# kaaEmonitor_2v01.net
KiCad netlist of a schematic drawn in EAGLE
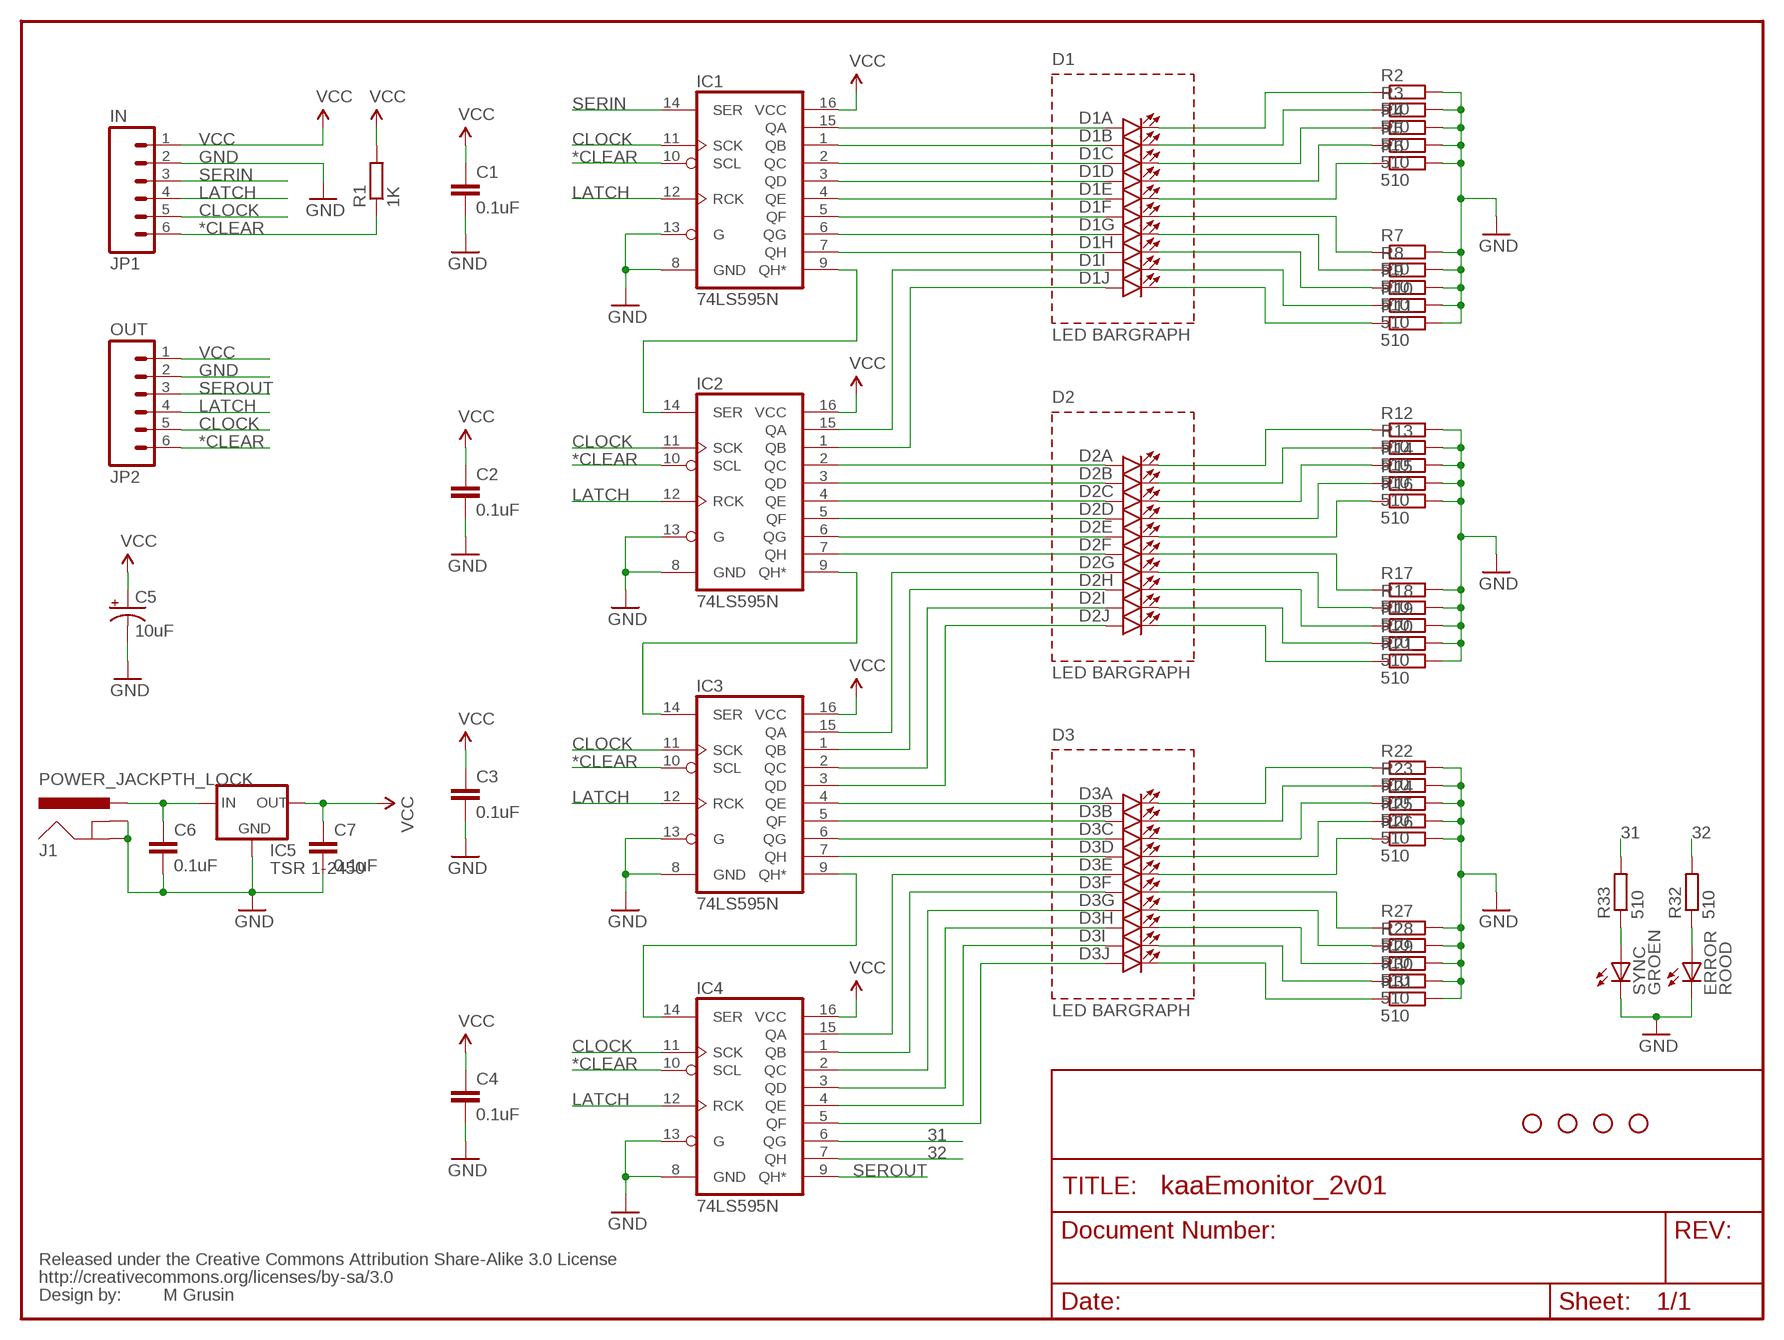
[diagram p0: schematic, sheet 1]

(export (version "E")
  (design (tool "Eeschema 10.0.6"))
  (components
    (comp (ref "C1")
      (value "0.1uF")
      (footprint "eagle-import:CAP-PTH-SMALL2")
      (libsource (lib "eagle-import") (part "CAPPTH2"))
    )
    (comp (ref "C2")
      (value "0.1uF")
      (footprint "eagle-import:CAP-PTH-SMALL2")
      (libsource (lib "eagle-import") (part "CAPPTH2"))
    )
    (comp (ref "C3")
      (value "0.1uF")
      (footprint "eagle-import:CAP-PTH-SMALL2")
      (libsource (lib "eagle-import") (part "CAPPTH2"))
    )
    (comp (ref "C4")
      (value "0.1uF")
      (footprint "eagle-import:CAP-PTH-SMALL2")
      (libsource (lib "eagle-import") (part "CAPPTH2"))
    )
    (comp (ref "C5")
      (value "10uF")
      (footprint "eagle-import:CPOL-RADIAL-10UF-25V")
      (libsource (lib "eagle-import") (part "CAP_POLPTH2"))
    )
    (comp (ref "C6")
      (value "0.1uF")
      (footprint "eagle-import:CAP-PTH-SMALL2")
      (libsource (lib "eagle-import") (part "CAPPTH2"))
    )
    (comp (ref "C7")
      (value "0.1uF")
      (footprint "eagle-import:CAP-PTH-SMALL2")
      (libsource (lib "eagle-import") (part "CAPPTH2"))
    )
    (comp (ref "D1")
      (value "LED_BARGRAPH_10")
      (footprint "eagle-import:LED_BARGAPH_10")
      (libsource (lib "eagle-import") (part "LED_BARGRAPH_10"))
    )
    (comp (ref "D2")
      (value "LED_BARGRAPH_10")
      (footprint "eagle-import:LED_BARGAPH_10")
      (libsource (lib "eagle-import") (part "LED_BARGRAPH_10"))
    )
    (comp (ref "D3")
      (value "LED_BARGRAPH_10")
      (footprint "eagle-import:LED_BARGAPH_10")
      (libsource (lib "eagle-import") (part "LED_BARGRAPH_10"))
    )
    (comp (ref "ERROR")
      (value "ROOD")
      (footprint "eagle-import:LED3MM")
      (libsource (lib "eagle-import") (part "LED3MM"))
    )
    (comp (ref "IC1")
      (value "74LS595N")
      (footprint "eagle-import:DIL16")
      (libsource (lib "eagle-import") (part "74595NLS"))
    )
    (comp (ref "IC2")
      (value "74LS595N")
      (footprint "eagle-import:DIL16")
      (libsource (lib "eagle-import") (part "74595NLS"))
    )
    (comp (ref "IC3")
      (value "74LS595N")
      (footprint "eagle-import:DIL16")
      (libsource (lib "eagle-import") (part "74595NLS"))
    )
    (comp (ref "IC4")
      (value "74LS595N")
      (footprint "eagle-import:DIL16")
      (libsource (lib "eagle-import") (part "74595NLS"))
    )
    (comp (ref "IC5")
      (value "TSR 1-2450")
      (footprint "eagle-import:TO220-IGO")
      (libsource (lib "eagle-import") (part "V_REG_78XXSINK"))
    )
    (comp (ref "J1")
      (value "POWER_JACKPTH_LOCK")
      (footprint "eagle-import:POWER_JACK_PTH_LOCK")
      (libsource (lib "eagle-import") (part "POWER_JACKPTH_LOCK"))
    )
    (comp (ref "JP1")
      (value "IN")
      (footprint "eagle-import:1X06")
      (libsource (lib "eagle-import") (part "M06SIP"))
    )
    (comp (ref "JP2")
      (value "OUT")
      (footprint "eagle-import:1X06")
      (libsource (lib "eagle-import") (part "M06SIP"))
    )
    (comp (ref "R1")
      (value "1K")
      (footprint "eagle-import:0204_5")
      (libsource (lib "eagle-import") (part "R-EU_0204/5"))
    )
    (comp (ref "R2")
      (value "510")
      (footprint "eagle-import:0204_5")
      (libsource (lib "eagle-import") (part "R-EU_0204/5"))
    )
    (comp (ref "R3")
      (value "510")
      (footprint "eagle-import:0204_5")
      (libsource (lib "eagle-import") (part "R-EU_0204/5"))
    )
    (comp (ref "R4")
      (value "510")
      (footprint "eagle-import:0204_5")
      (libsource (lib "eagle-import") (part "R-EU_0204/5"))
    )
    (comp (ref "R5")
      (value "510")
      (footprint "eagle-import:0204_5")
      (libsource (lib "eagle-import") (part "R-EU_0204/5"))
    )
    (comp (ref "R6")
      (value "510")
      (footprint "eagle-import:0204_5")
      (libsource (lib "eagle-import") (part "R-EU_0204/5"))
    )
    (comp (ref "R7")
      (value "510")
      (footprint "eagle-import:0204_5")
      (libsource (lib "eagle-import") (part "R-EU_0204/5"))
    )
    (comp (ref "R8")
      (value "510")
      (footprint "eagle-import:0204_5")
      (libsource (lib "eagle-import") (part "R-EU_0204/5"))
    )
    (comp (ref "R9")
      (value "510")
      (footprint "eagle-import:0204_5")
      (libsource (lib "eagle-import") (part "R-EU_0204/5"))
    )
    (comp (ref "R10")
      (value "510")
      (footprint "eagle-import:0204_5")
      (libsource (lib "eagle-import") (part "R-EU_0204/5"))
    )
    (comp (ref "R11")
      (value "510")
      (footprint "eagle-import:0204_5")
      (libsource (lib "eagle-import") (part "R-EU_0204/5"))
    )
    (comp (ref "R12")
      (value "510")
      (footprint "eagle-import:0204_5")
      (libsource (lib "eagle-import") (part "R-EU_0204/5"))
    )
    (comp (ref "R13")
      (value "510")
      (footprint "eagle-import:0204_5")
      (libsource (lib "eagle-import") (part "R-EU_0204/5"))
    )
    (comp (ref "R14")
      (value "510")
      (footprint "eagle-import:0204_5")
      (libsource (lib "eagle-import") (part "R-EU_0204/5"))
    )
    (comp (ref "R15")
      (value "510")
      (footprint "eagle-import:0204_5")
      (libsource (lib "eagle-import") (part "R-EU_0204/5"))
    )
    (comp (ref "R16")
      (value "510")
      (footprint "eagle-import:0204_5")
      (libsource (lib "eagle-import") (part "R-EU_0204/5"))
    )
    (comp (ref "R17")
      (value "510")
      (footprint "eagle-import:0204_5")
      (libsource (lib "eagle-import") (part "R-EU_0204/5"))
    )
    (comp (ref "R18")
      (value "510")
      (footprint "eagle-import:0204_5")
      (libsource (lib "eagle-import") (part "R-EU_0204/5"))
    )
    (comp (ref "R19")
      (value "510")
      (footprint "eagle-import:0204_5")
      (libsource (lib "eagle-import") (part "R-EU_0204/5"))
    )
    (comp (ref "R20")
      (value "510")
      (footprint "eagle-import:0204_5")
      (libsource (lib "eagle-import") (part "R-EU_0204/5"))
    )
    (comp (ref "R21")
      (value "510")
      (footprint "eagle-import:0204_5")
      (libsource (lib "eagle-import") (part "R-EU_0204/5"))
    )
    (comp (ref "R22")
      (value "510")
      (footprint "eagle-import:0204_5")
      (libsource (lib "eagle-import") (part "R-EU_0204/5"))
    )
    (comp (ref "R23")
      (value "510")
      (footprint "eagle-import:0204_5")
      (libsource (lib "eagle-import") (part "R-EU_0204/5"))
    )
    (comp (ref "R24")
      (value "510")
      (footprint "eagle-import:0204_5")
      (libsource (lib "eagle-import") (part "R-EU_0204/5"))
    )
    (comp (ref "R25")
      (value "510")
      (footprint "eagle-import:0204_5")
      (libsource (lib "eagle-import") (part "R-EU_0204/5"))
    )
    (comp (ref "R26")
      (value "510")
      (footprint "eagle-import:0204_5")
      (libsource (lib "eagle-import") (part "R-EU_0204/5"))
    )
    (comp (ref "R27")
      (value "510")
      (footprint "eagle-import:0204_5")
      (libsource (lib "eagle-import") (part "R-EU_0204/5"))
    )
    (comp (ref "R28")
      (value "510")
      (footprint "eagle-import:0204_5")
      (libsource (lib "eagle-import") (part "R-EU_0204/5"))
    )
    (comp (ref "R29")
      (value "510")
      (footprint "eagle-import:0204_5")
      (libsource (lib "eagle-import") (part "R-EU_0204/5"))
    )
    (comp (ref "R30")
      (value "510")
      (footprint "eagle-import:0204_5")
      (libsource (lib "eagle-import") (part "R-EU_0204/5"))
    )
    (comp (ref "R31")
      (value "510")
      (footprint "eagle-import:0204_5")
      (libsource (lib "eagle-import") (part "R-EU_0204/5"))
    )
    (comp (ref "R32")
      (value "510")
      (footprint "eagle-import:0204_5")
      (libsource (lib "eagle-import") (part "R-EU_0204/5"))
    )
    (comp (ref "R33")
      (value "510")
      (footprint "eagle-import:0204_5")
      (libsource (lib "eagle-import") (part "R-EU_0204/5"))
    )
    (comp (ref "SO1")
      (value "STAND-OFF")
      (footprint "eagle-import:STAND-OFF")
      (libsource (lib "eagle-import") (part "STAND-OFF"))
    )
    (comp (ref "SO2")
      (value "STAND-OFF")
      (footprint "eagle-import:STAND-OFF")
      (libsource (lib "eagle-import") (part "STAND-OFF"))
    )
    (comp (ref "SO3")
      (value "STAND-OFF")
      (footprint "eagle-import:STAND-OFF")
      (libsource (lib "eagle-import") (part "STAND-OFF"))
    )
    (comp (ref "SO4")
      (value "STAND-OFF")
      (footprint "eagle-import:STAND-OFF")
      (libsource (lib "eagle-import") (part "STAND-OFF"))
    )
    (comp (ref "SYNC")
      (value "GROEN")
      (footprint "eagle-import:LED3MM")
      (libsource (lib "eagle-import") (part "LED3MM"))
    )
    (comp (ref "U$6")
      (value "CREATIVE_COMMONS")
      (footprint "eagle-import:CREATIVE_COMMONS")
      (libsource (lib "eagle-import") (part "CREATIVE_COMMONS"))
    )
  )
  (nets
    (net (code "1") (name "/*CLEAR") (class "Default")
      (node (ref "IC1") (pin "10") (pinfunction "SCL_10") (pintype "input"))
      (node (ref "IC2") (pin "10") (pinfunction "SCL_10") (pintype "input"))
      (node (ref "IC3") (pin "10") (pinfunction "SCL_10") (pintype "input"))
      (node (ref "IC4") (pin "10") (pinfunction "SCL_10") (pintype "input"))
      (node (ref "JP1") (pin "6") (pinfunction "6_6") (pintype "passive"))
      (node (ref "JP2") (pin "6") (pinfunction "6_6") (pintype "passive"))
      (node (ref "R1") (pin "1") (pinfunction "1_1") (pintype "passive"))
    )
    (net (code "2") (name "/31") (class "Default")
      (node (ref "IC4") (pin "6") (pinfunction "QG_6") (pintype "tri_state"))
      (node (ref "R33") (pin "2") (pinfunction "2_2") (pintype "passive"))
    )
    (net (code "3") (name "/32") (class "Default")
      (node (ref "IC4") (pin "7") (pinfunction "QH_7") (pintype "tri_state"))
      (node (ref "R32") (pin "2") (pinfunction "2_2") (pintype "passive"))
    )
    (net (code "4") (name "/CLOCK") (class "Default")
      (node (ref "IC1") (pin "11") (pinfunction "SCK_11") (pintype "input"))
      (node (ref "IC2") (pin "11") (pinfunction "SCK_11") (pintype "input"))
      (node (ref "IC3") (pin "11") (pinfunction "SCK_11") (pintype "input"))
      (node (ref "IC4") (pin "11") (pinfunction "SCK_11") (pintype "input"))
      (node (ref "JP1") (pin "5") (pinfunction "5_5") (pintype "passive"))
      (node (ref "JP2") (pin "5") (pinfunction "5_5") (pintype "passive"))
    )
    (net (code "5") (name "/LATCH") (class "Default")
      (node (ref "IC1") (pin "12") (pinfunction "RCK_12") (pintype "input"))
      (node (ref "IC2") (pin "12") (pinfunction "RCK_12") (pintype "input"))
      (node (ref "IC3") (pin "12") (pinfunction "RCK_12") (pintype "input"))
      (node (ref "IC4") (pin "12") (pinfunction "RCK_12") (pintype "input"))
      (node (ref "JP1") (pin "4") (pinfunction "4_4") (pintype "passive"))
      (node (ref "JP2") (pin "4") (pinfunction "4_4") (pintype "passive"))
    )
    (net (code "6") (name "/SERIN") (class "Default")
      (node (ref "IC1") (pin "14") (pinfunction "SER_14") (pintype "input"))
      (node (ref "JP1") (pin "3") (pinfunction "3_3") (pintype "passive"))
    )
    (net (code "7") (name "/SEROUT") (class "Default")
      (node (ref "IC4") (pin "9") (pinfunction "QH*_9") (pintype "tri_state"))
      (node (ref "JP2") (pin "3") (pinfunction "3_3") (pintype "passive"))
    )
    (net (code "8") (name "GND") (class "Default")
      (node (ref "C1") (pin "2") (pinfunction "2_2") (pintype "passive"))
      (node (ref "C2") (pin "2") (pinfunction "2_2") (pintype "passive"))
      (node (ref "C3") (pin "2") (pinfunction "2_2") (pintype "passive"))
      (node (ref "C4") (pin "2") (pinfunction "2_2") (pintype "passive"))
      (node (ref "C5") (pin "2") (pinfunction "-_2") (pintype "passive"))
      (node (ref "C6") (pin "2") (pinfunction "2_2") (pintype "passive"))
      (node (ref "C7") (pin "2") (pinfunction "2_2") (pintype "passive"))
      (node (ref "ERROR") (pin "K") (pinfunction "C_K") (pintype "passive"))
      (node (ref "IC1") (pin "13") (pinfunction "G_13") (pintype "input"))
      (node (ref "IC1") (pin "8") (pinfunction "GND_8") (pintype "power_in"))
      (node (ref "IC2") (pin "13") (pinfunction "G_13") (pintype "input"))
      (node (ref "IC2") (pin "8") (pinfunction "GND_8") (pintype "power_in"))
      (node (ref "IC3") (pin "13") (pinfunction "G_13") (pintype "input"))
      (node (ref "IC3") (pin "8") (pinfunction "GND_8") (pintype "power_in"))
      (node (ref "IC4") (pin "13") (pinfunction "G_13") (pintype "input"))
      (node (ref "IC4") (pin "8") (pinfunction "GND_8") (pintype "power_in"))
      (node (ref "IC5") (pin "GND") (pinfunction "GND_GND") (pintype "input"))
      (node (ref "J1") (pin "GND") (pinfunction "GND_GND") (pintype "bidirectional"))
      (node (ref "J1") (pin "GNDBREAK") (pinfunction "GNDBREAK_GNDBREAK") (pintype "bidirectional"))
      (node (ref "JP1") (pin "2") (pinfunction "2_2") (pintype "passive"))
      (node (ref "JP2") (pin "2") (pinfunction "2_2") (pintype "passive"))
      (node (ref "R10") (pin "2") (pinfunction "2_2") (pintype "passive"))
      (node (ref "R11") (pin "2") (pinfunction "2_2") (pintype "passive"))
      (node (ref "R12") (pin "2") (pinfunction "2_2") (pintype "passive"))
      (node (ref "R13") (pin "2") (pinfunction "2_2") (pintype "passive"))
      (node (ref "R14") (pin "2") (pinfunction "2_2") (pintype "passive"))
      (node (ref "R15") (pin "2") (pinfunction "2_2") (pintype "passive"))
      (node (ref "R16") (pin "2") (pinfunction "2_2") (pintype "passive"))
      (node (ref "R17") (pin "2") (pinfunction "2_2") (pintype "passive"))
      (node (ref "R18") (pin "2") (pinfunction "2_2") (pintype "passive"))
      (node (ref "R19") (pin "2") (pinfunction "2_2") (pintype "passive"))
      (node (ref "R2") (pin "2") (pinfunction "2_2") (pintype "passive"))
      (node (ref "R20") (pin "2") (pinfunction "2_2") (pintype "passive"))
      (node (ref "R21") (pin "2") (pinfunction "2_2") (pintype "passive"))
      (node (ref "R22") (pin "2") (pinfunction "2_2") (pintype "passive"))
      (node (ref "R23") (pin "2") (pinfunction "2_2") (pintype "passive"))
      (node (ref "R24") (pin "2") (pinfunction "2_2") (pintype "passive"))
      (node (ref "R25") (pin "2") (pinfunction "2_2") (pintype "passive"))
      (node (ref "R26") (pin "2") (pinfunction "2_2") (pintype "passive"))
      (node (ref "R27") (pin "2") (pinfunction "2_2") (pintype "passive"))
      (node (ref "R28") (pin "2") (pinfunction "2_2") (pintype "passive"))
      (node (ref "R29") (pin "2") (pinfunction "2_2") (pintype "passive"))
      (node (ref "R3") (pin "2") (pinfunction "2_2") (pintype "passive"))
      (node (ref "R30") (pin "2") (pinfunction "2_2") (pintype "passive"))
      (node (ref "R31") (pin "2") (pinfunction "2_2") (pintype "passive"))
      (node (ref "R4") (pin "2") (pinfunction "2_2") (pintype "passive"))
      (node (ref "R5") (pin "2") (pinfunction "2_2") (pintype "passive"))
      (node (ref "R6") (pin "2") (pinfunction "2_2") (pintype "passive"))
      (node (ref "R7") (pin "2") (pinfunction "2_2") (pintype "passive"))
      (node (ref "R8") (pin "2") (pinfunction "2_2") (pintype "passive"))
      (node (ref "R9") (pin "2") (pinfunction "2_2") (pintype "passive"))
      (node (ref "SYNC") (pin "K") (pinfunction "C_K") (pintype "passive"))
    )
    (net (code "9") (name "Net-(C6-Pad1)") (class "Default")
      (node (ref "C6") (pin "1") (pinfunction "1_1") (pintype "passive"))
      (node (ref "IC5") (pin "IN") (pinfunction "IN_IN") (pintype "input"))
      (node (ref "J1") (pin "PWR") (pinfunction "PWR_PWR") (pintype "bidirectional"))
    )
    (net (code "10") (name "Net-(D1A-A)") (class "Default")
      (node (ref "D1") (pin "1") (pinfunction "A_1") (pintype "passive"))
      (node (ref "IC1") (pin "15") (pinfunction "QA_15") (pintype "tri_state"))
    )
    (net (code "11") (name "Net-(D1A-C)") (class "Default")
      (node (ref "D1") (pin "20") (pinfunction "C_20") (pintype "passive"))
      (node (ref "R2") (pin "1") (pinfunction "1_1") (pintype "passive"))
    )
    (net (code "12") (name "Net-(D1B-A)") (class "Default")
      (node (ref "D1") (pin "2") (pinfunction "A_2") (pintype "passive"))
      (node (ref "IC1") (pin "1") (pinfunction "QB_1") (pintype "tri_state"))
    )
    (net (code "13") (name "Net-(D1B-C)") (class "Default")
      (node (ref "D1") (pin "19") (pinfunction "C_19") (pintype "passive"))
      (node (ref "R3") (pin "1") (pinfunction "1_1") (pintype "passive"))
    )
    (net (code "14") (name "Net-(D1C-A)") (class "Default")
      (node (ref "D1") (pin "3") (pinfunction "A_3") (pintype "passive"))
      (node (ref "IC1") (pin "2") (pinfunction "QC_2") (pintype "tri_state"))
    )
    (net (code "15") (name "Net-(D1C-C)") (class "Default")
      (node (ref "D1") (pin "18") (pinfunction "C_18") (pintype "passive"))
      (node (ref "R4") (pin "1") (pinfunction "1_1") (pintype "passive"))
    )
    (net (code "16") (name "Net-(D1D-A)") (class "Default")
      (node (ref "D1") (pin "4") (pinfunction "A_4") (pintype "passive"))
      (node (ref "IC1") (pin "3") (pinfunction "QD_3") (pintype "tri_state"))
    )
    (net (code "17") (name "Net-(D1D-C)") (class "Default")
      (node (ref "D1") (pin "17") (pinfunction "C_17") (pintype "passive"))
      (node (ref "R5") (pin "1") (pinfunction "1_1") (pintype "passive"))
    )
    (net (code "18") (name "Net-(D1E-A)") (class "Default")
      (node (ref "D1") (pin "5") (pinfunction "A_5") (pintype "passive"))
      (node (ref "IC1") (pin "4") (pinfunction "QE_4") (pintype "tri_state"))
    )
    (net (code "19") (name "Net-(D1E-C)") (class "Default")
      (node (ref "D1") (pin "16") (pinfunction "C_16") (pintype "passive"))
      (node (ref "R6") (pin "1") (pinfunction "1_1") (pintype "passive"))
    )
    (net (code "20") (name "Net-(D1F-A)") (class "Default")
      (node (ref "D1") (pin "6") (pinfunction "A_6") (pintype "passive"))
      (node (ref "IC1") (pin "5") (pinfunction "QF_5") (pintype "tri_state"))
    )
    (net (code "21") (name "Net-(D1F-C)") (class "Default")
      (node (ref "D1") (pin "15") (pinfunction "C_15") (pintype "passive"))
      (node (ref "R7") (pin "1") (pinfunction "1_1") (pintype "passive"))
    )
    (net (code "22") (name "Net-(D1G-A)") (class "Default")
      (node (ref "D1") (pin "7") (pinfunction "A_7") (pintype "passive"))
      (node (ref "IC1") (pin "6") (pinfunction "QG_6") (pintype "tri_state"))
    )
    (net (code "23") (name "Net-(D1G-C)") (class "Default")
      (node (ref "D1") (pin "14") (pinfunction "C_14") (pintype "passive"))
      (node (ref "R8") (pin "1") (pinfunction "1_1") (pintype "passive"))
    )
    (net (code "24") (name "Net-(D1H-A)") (class "Default")
      (node (ref "D1") (pin "8") (pinfunction "A_8") (pintype "passive"))
      (node (ref "IC1") (pin "7") (pinfunction "QH_7") (pintype "tri_state"))
    )
    (net (code "25") (name "Net-(D1H-C)") (class "Default")
      (node (ref "D1") (pin "13") (pinfunction "C_13") (pintype "passive"))
      (node (ref "R9") (pin "1") (pinfunction "1_1") (pintype "passive"))
    )
    (net (code "26") (name "Net-(D1I-A)") (class "Default")
      (node (ref "D1") (pin "9") (pinfunction "A_9") (pintype "passive"))
      (node (ref "IC2") (pin "15") (pinfunction "QA_15") (pintype "tri_state"))
    )
    (net (code "27") (name "Net-(D1I-C)") (class "Default")
      (node (ref "D1") (pin "12") (pinfunction "C_12") (pintype "passive"))
      (node (ref "R10") (pin "1") (pinfunction "1_1") (pintype "passive"))
    )
    (net (code "28") (name "Net-(D1J-A)") (class "Default")
      (node (ref "D1") (pin "10") (pinfunction "A_10") (pintype "passive"))
      (node (ref "IC2") (pin "1") (pinfunction "QB_1") (pintype "tri_state"))
    )
    (net (code "29") (name "Net-(D1J-C)") (class "Default")
      (node (ref "D1") (pin "11") (pinfunction "C_11") (pintype "passive"))
      (node (ref "R11") (pin "1") (pinfunction "1_1") (pintype "passive"))
    )
    (net (code "30") (name "Net-(D2A-A)") (class "Default")
      (node (ref "D2") (pin "1") (pinfunction "A_1") (pintype "passive"))
      (node (ref "IC2") (pin "2") (pinfunction "QC_2") (pintype "tri_state"))
    )
    (net (code "31") (name "Net-(D2A-C)") (class "Default")
      (node (ref "D2") (pin "20") (pinfunction "C_20") (pintype "passive"))
      (node (ref "R12") (pin "1") (pinfunction "1_1") (pintype "passive"))
    )
    (net (code "32") (name "Net-(D2B-A)") (class "Default")
      (node (ref "D2") (pin "2") (pinfunction "A_2") (pintype "passive"))
      (node (ref "IC2") (pin "3") (pinfunction "QD_3") (pintype "tri_state"))
    )
    (net (code "33") (name "Net-(D2B-C)") (class "Default")
      (node (ref "D2") (pin "19") (pinfunction "C_19") (pintype "passive"))
      (node (ref "R13") (pin "1") (pinfunction "1_1") (pintype "passive"))
    )
    (net (code "34") (name "Net-(D2C-A)") (class "Default")
      (node (ref "D2") (pin "3") (pinfunction "A_3") (pintype "passive"))
      (node (ref "IC2") (pin "4") (pinfunction "QE_4") (pintype "tri_state"))
    )
    (net (code "35") (name "Net-(D2C-C)") (class "Default")
      (node (ref "D2") (pin "18") (pinfunction "C_18") (pintype "passive"))
      (node (ref "R14") (pin "1") (pinfunction "1_1") (pintype "passive"))
    )
    (net (code "36") (name "Net-(D2D-A)") (class "Default")
      (node (ref "D2") (pin "4") (pinfunction "A_4") (pintype "passive"))
      (node (ref "IC2") (pin "5") (pinfunction "QF_5") (pintype "tri_state"))
    )
    (net (code "37") (name "Net-(D2D-C)") (class "Default")
      (node (ref "D2") (pin "17") (pinfunction "C_17") (pintype "passive"))
      (node (ref "R15") (pin "1") (pinfunction "1_1") (pintype "passive"))
    )
    (net (code "38") (name "Net-(D2E-A)") (class "Default")
      (node (ref "D2") (pin "5") (pinfunction "A_5") (pintype "passive"))
      (node (ref "IC2") (pin "6") (pinfunction "QG_6") (pintype "tri_state"))
    )
    (net (code "39") (name "Net-(D2E-C)") (class "Default")
      (node (ref "D2") (pin "16") (pinfunction "C_16") (pintype "passive"))
      (node (ref "R16") (pin "1") (pinfunction "1_1") (pintype "passive"))
    )
    (net (code "40") (name "Net-(D2F-A)") (class "Default")
      (node (ref "D2") (pin "6") (pinfunction "A_6") (pintype "passive"))
      (node (ref "IC2") (pin "7") (pinfunction "QH_7") (pintype "tri_state"))
    )
    (net (code "41") (name "Net-(D2F-C)") (class "Default")
      (node (ref "D2") (pin "15") (pinfunction "C_15") (pintype "passive"))
      (node (ref "R17") (pin "1") (pinfunction "1_1") (pintype "passive"))
    )
    (net (code "42") (name "Net-(D2G-A)") (class "Default")
      (node (ref "D2") (pin "7") (pinfunction "A_7") (pintype "passive"))
      (node (ref "IC3") (pin "15") (pinfunction "QA_15") (pintype "tri_state"))
    )
    (net (code "43") (name "Net-(D2G-C)") (class "Default")
      (node (ref "D2") (pin "14") (pinfunction "C_14") (pintype "passive"))
      (node (ref "R18") (pin "1") (pinfunction "1_1") (pintype "passive"))
    )
    (net (code "44") (name "Net-(D2H-A)") (class "Default")
      (node (ref "D2") (pin "8") (pinfunction "A_8") (pintype "passive"))
      (node (ref "IC3") (pin "1") (pinfunction "QB_1") (pintype "tri_state"))
    )
    (net (code "45") (name "Net-(D2H-C)") (class "Default")
      (node (ref "D2") (pin "13") (pinfunction "C_13") (pintype "passive"))
      (node (ref "R19") (pin "1") (pinfunction "1_1") (pintype "passive"))
    )
    (net (code "46") (name "Net-(D2I-A)") (class "Default")
      (node (ref "D2") (pin "9") (pinfunction "A_9") (pintype "passive"))
      (node (ref "IC3") (pin "2") (pinfunction "QC_2") (pintype "tri_state"))
    )
    (net (code "47") (name "Net-(D2I-C)") (class "Default")
      (node (ref "D2") (pin "12") (pinfunction "C_12") (pintype "passive"))
      (node (ref "R20") (pin "1") (pinfunction "1_1") (pintype "passive"))
    )
    (net (code "48") (name "Net-(D2J-A)") (class "Default")
      (node (ref "D2") (pin "10") (pinfunction "A_10") (pintype "passive"))
      (node (ref "IC3") (pin "3") (pinfunction "QD_3") (pintype "tri_state"))
    )
    (net (code "49") (name "Net-(D2J-C)") (class "Default")
      (node (ref "D2") (pin "11") (pinfunction "C_11") (pintype "passive"))
      (node (ref "R21") (pin "1") (pinfunction "1_1") (pintype "passive"))
    )
    (net (code "50") (name "Net-(D3A-A)") (class "Default")
      (node (ref "D3") (pin "1") (pinfunction "A_1") (pintype "passive"))
      (node (ref "IC3") (pin "4") (pinfunction "QE_4") (pintype "tri_state"))
    )
    (net (code "51") (name "Net-(D3A-C)") (class "Default")
      (node (ref "D3") (pin "20") (pinfunction "C_20") (pintype "passive"))
      (node (ref "R22") (pin "1") (pinfunction "1_1") (pintype "passive"))
    )
    (net (code "52") (name "Net-(D3B-A)") (class "Default")
      (node (ref "D3") (pin "2") (pinfunction "A_2") (pintype "passive"))
      (node (ref "IC3") (pin "5") (pinfunction "QF_5") (pintype "tri_state"))
    )
    (net (code "53") (name "Net-(D3B-C)") (class "Default")
      (node (ref "D3") (pin "19") (pinfunction "C_19") (pintype "passive"))
      (node (ref "R23") (pin "1") (pinfunction "1_1") (pintype "passive"))
    )
    (net (code "54") (name "Net-(D3C-A)") (class "Default")
      (node (ref "D3") (pin "3") (pinfunction "A_3") (pintype "passive"))
      (node (ref "IC3") (pin "6") (pinfunction "QG_6") (pintype "tri_state"))
    )
    (net (code "55") (name "Net-(D3C-C)") (class "Default")
      (node (ref "D3") (pin "18") (pinfunction "C_18") (pintype "passive"))
      (node (ref "R24") (pin "1") (pinfunction "1_1") (pintype "passive"))
    )
    (net (code "56") (name "Net-(D3D-A)") (class "Default")
      (node (ref "D3") (pin "4") (pinfunction "A_4") (pintype "passive"))
      (node (ref "IC3") (pin "7") (pinfunction "QH_7") (pintype "tri_state"))
    )
    (net (code "57") (name "Net-(D3D-C)") (class "Default")
      (node (ref "D3") (pin "17") (pinfunction "C_17") (pintype "passive"))
      (node (ref "R25") (pin "1") (pinfunction "1_1") (pintype "passive"))
    )
    (net (code "58") (name "Net-(D3E-A)") (class "Default")
      (node (ref "D3") (pin "5") (pinfunction "A_5") (pintype "passive"))
      (node (ref "IC4") (pin "15") (pinfunction "QA_15") (pintype "tri_state"))
    )
    (net (code "59") (name "Net-(D3E-C)") (class "Default")
      (node (ref "D3") (pin "16") (pinfunction "C_16") (pintype "passive"))
      (node (ref "R26") (pin "1") (pinfunction "1_1") (pintype "passive"))
    )
    (net (code "60") (name "Net-(D3F-A)") (class "Default")
      (node (ref "D3") (pin "6") (pinfunction "A_6") (pintype "passive"))
      (node (ref "IC4") (pin "1") (pinfunction "QB_1") (pintype "tri_state"))
    )
    (net (code "61") (name "Net-(D3F-C)") (class "Default")
      (node (ref "D3") (pin "15") (pinfunction "C_15") (pintype "passive"))
      (node (ref "R27") (pin "1") (pinfunction "1_1") (pintype "passive"))
    )
    (net (code "62") (name "Net-(D3G-A)") (class "Default")
      (node (ref "D3") (pin "7") (pinfunction "A_7") (pintype "passive"))
      (node (ref "IC4") (pin "2") (pinfunction "QC_2") (pintype "tri_state"))
    )
    (net (code "63") (name "Net-(D3G-C)") (class "Default")
      (node (ref "D3") (pin "14") (pinfunction "C_14") (pintype "passive"))
      (node (ref "R28") (pin "1") (pinfunction "1_1") (pintype "passive"))
    )
    (net (code "64") (name "Net-(D3H-A)") (class "Default")
      (node (ref "D3") (pin "8") (pinfunction "A_8") (pintype "passive"))
      (node (ref "IC4") (pin "3") (pinfunction "QD_3") (pintype "tri_state"))
    )
    (net (code "65") (name "Net-(D3H-C)") (class "Default")
      (node (ref "D3") (pin "13") (pinfunction "C_13") (pintype "passive"))
      (node (ref "R29") (pin "1") (pinfunction "1_1") (pintype "passive"))
    )
    (net (code "66") (name "Net-(D3I-A)") (class "Default")
      (node (ref "D3") (pin "9") (pinfunction "A_9") (pintype "passive"))
      (node (ref "IC4") (pin "4") (pinfunction "QE_4") (pintype "tri_state"))
    )
    (net (code "67") (name "Net-(D3I-C)") (class "Default")
      (node (ref "D3") (pin "12") (pinfunction "C_12") (pintype "passive"))
      (node (ref "R30") (pin "1") (pinfunction "1_1") (pintype "passive"))
    )
    (net (code "68") (name "Net-(D3J-A)") (class "Default")
      (node (ref "D3") (pin "10") (pinfunction "A_10") (pintype "passive"))
      (node (ref "IC4") (pin "5") (pinfunction "QF_5") (pintype "tri_state"))
    )
    (net (code "69") (name "Net-(D3J-C)") (class "Default")
      (node (ref "D3") (pin "11") (pinfunction "C_11") (pintype "passive"))
      (node (ref "R31") (pin "1") (pinfunction "1_1") (pintype "passive"))
    )
    (net (code "70") (name "Net-(ERROR-PadA)") (class "Default")
      (node (ref "ERROR") (pin "A") (pinfunction "A_A") (pintype "passive"))
      (node (ref "R32") (pin "1") (pinfunction "1_1") (pintype "passive"))
    )
    (net (code "71") (name "Net-(IC1-QH*)") (class "Default")
      (node (ref "IC1") (pin "9") (pinfunction "QH*_9") (pintype "tri_state"))
      (node (ref "IC2") (pin "14") (pinfunction "SER_14") (pintype "input"))
    )
    (net (code "72") (name "Net-(IC2-QH*)") (class "Default")
      (node (ref "IC2") (pin "9") (pinfunction "QH*_9") (pintype "tri_state"))
      (node (ref "IC3") (pin "14") (pinfunction "SER_14") (pintype "input"))
    )
    (net (code "73") (name "Net-(IC3-QH*)") (class "Default")
      (node (ref "IC3") (pin "9") (pinfunction "QH*_9") (pintype "tri_state"))
      (node (ref "IC4") (pin "14") (pinfunction "SER_14") (pintype "input"))
    )
    (net (code "74") (name "Net-(R33-Pad1)") (class "Default")
      (node (ref "R33") (pin "1") (pinfunction "1_1") (pintype "passive"))
      (node (ref "SYNC") (pin "A") (pinfunction "A_A") (pintype "passive"))
    )
    (net (code "75") (name "VCC") (class "Default")
      (node (ref "C1") (pin "1") (pinfunction "1_1") (pintype "passive"))
      (node (ref "C2") (pin "1") (pinfunction "1_1") (pintype "passive"))
      (node (ref "C3") (pin "1") (pinfunction "1_1") (pintype "passive"))
      (node (ref "C4") (pin "1") (pinfunction "1_1") (pintype "passive"))
      (node (ref "C5") (pin "1") (pinfunction "+_1") (pintype "passive"))
      (node (ref "C7") (pin "1") (pinfunction "1_1") (pintype "passive"))
      (node (ref "IC1") (pin "16") (pinfunction "VCC_16") (pintype "power_in"))
      (node (ref "IC2") (pin "16") (pinfunction "VCC_16") (pintype "power_in"))
      (node (ref "IC3") (pin "16") (pinfunction "VCC_16") (pintype "power_in"))
      (node (ref "IC4") (pin "16") (pinfunction "VCC_16") (pintype "power_in"))
      (node (ref "IC5") (pin "OUT") (pinfunction "OUT_OUT") (pintype "output"))
      (node (ref "JP1") (pin "1") (pinfunction "1_1") (pintype "passive"))
      (node (ref "JP2") (pin "1") (pinfunction "1_1") (pintype "passive"))
      (node (ref "R1") (pin "2") (pinfunction "2_2") (pintype "passive"))
    )
  )
)
